# TSOC_GROVEY_I2CHUB_R1_0.net
KiCad netlist of a schematic drawn in EAGLE
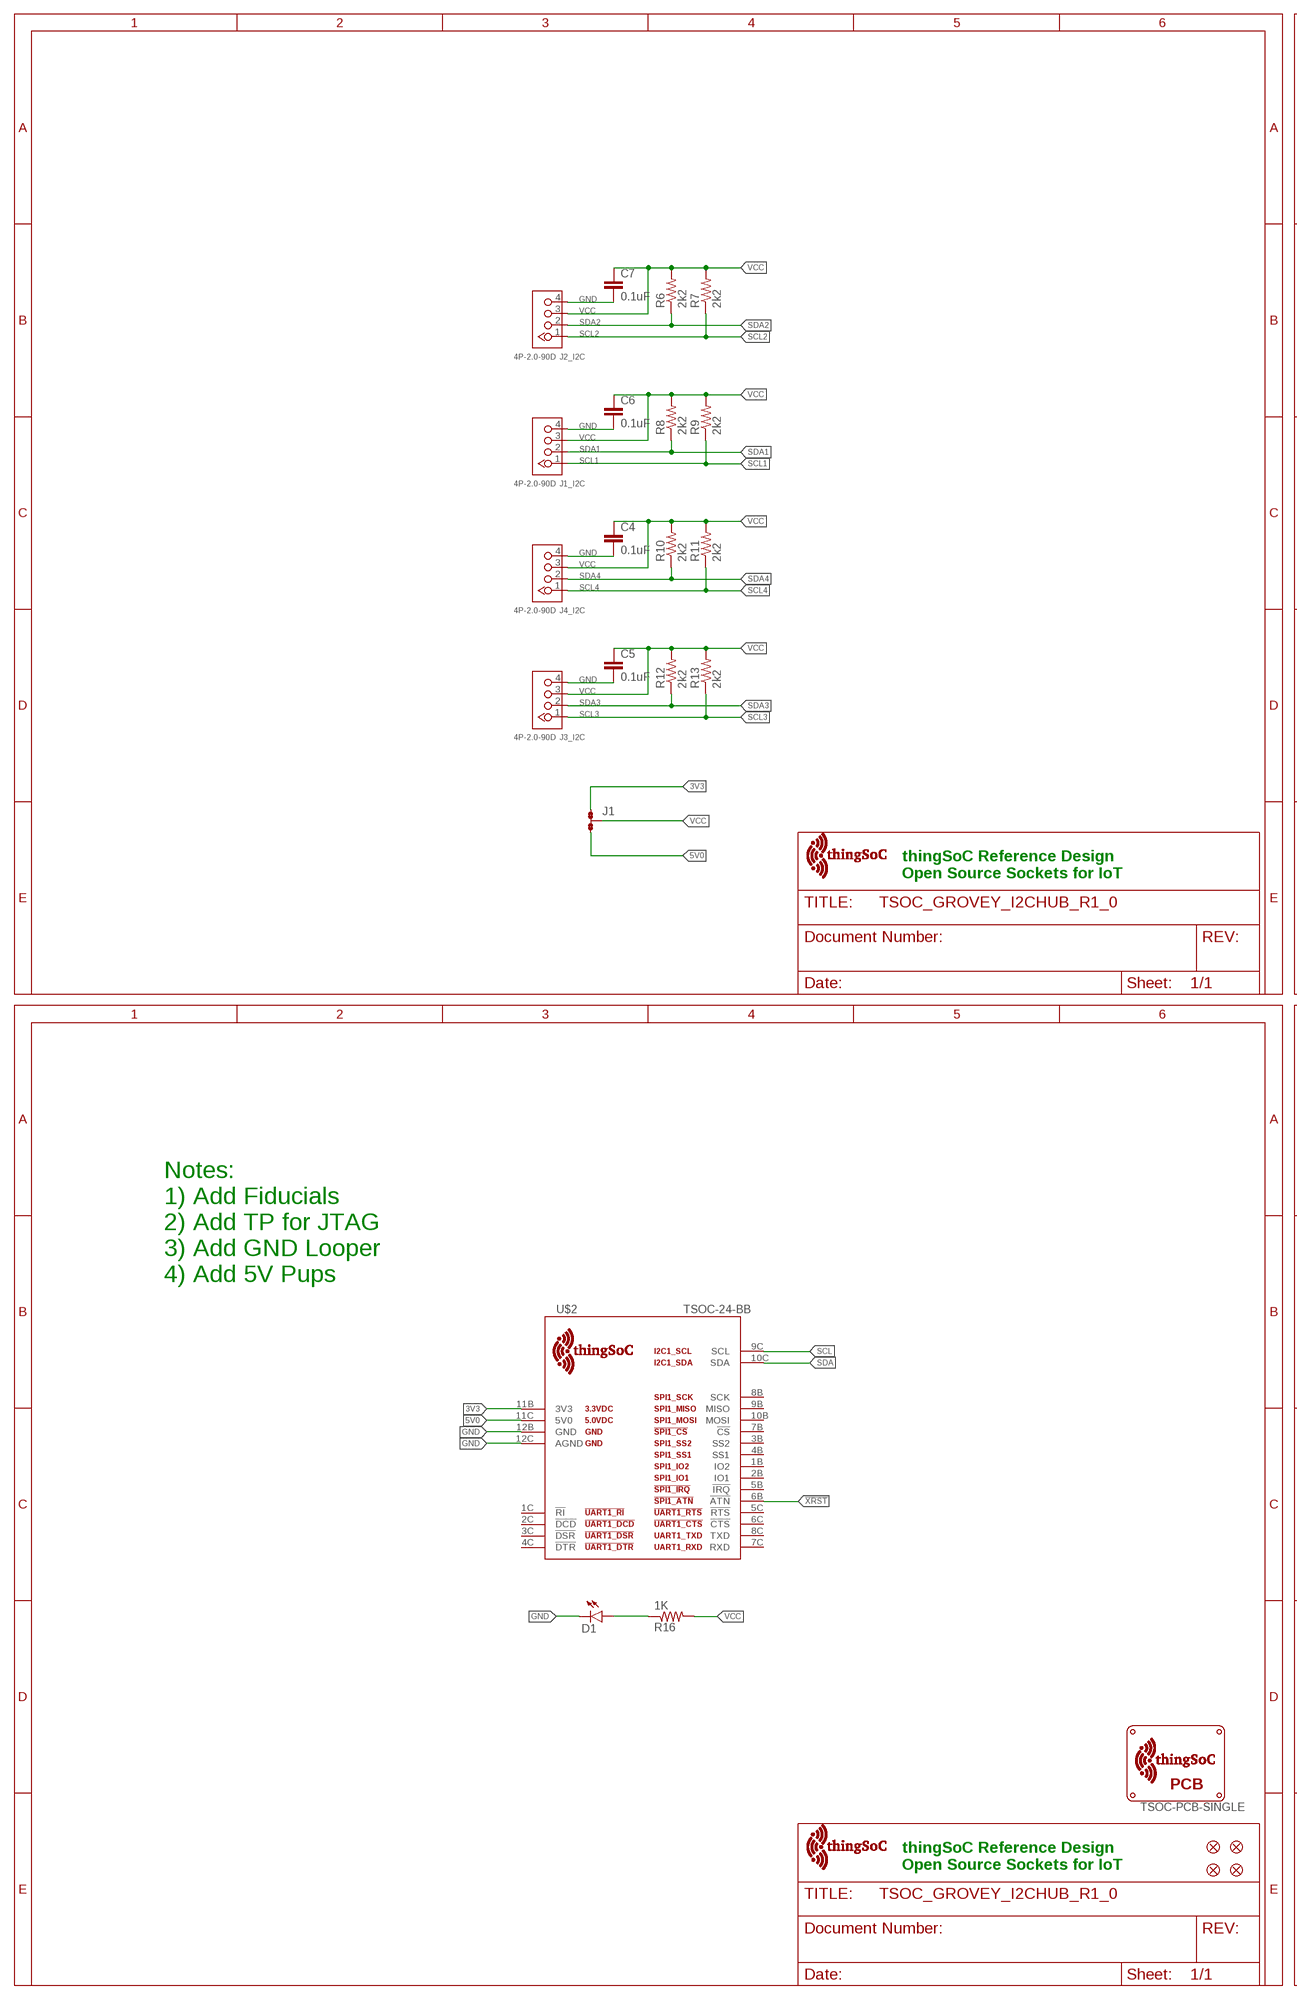
[diagram p0: schematic, sheet 1, part 1 of 2]
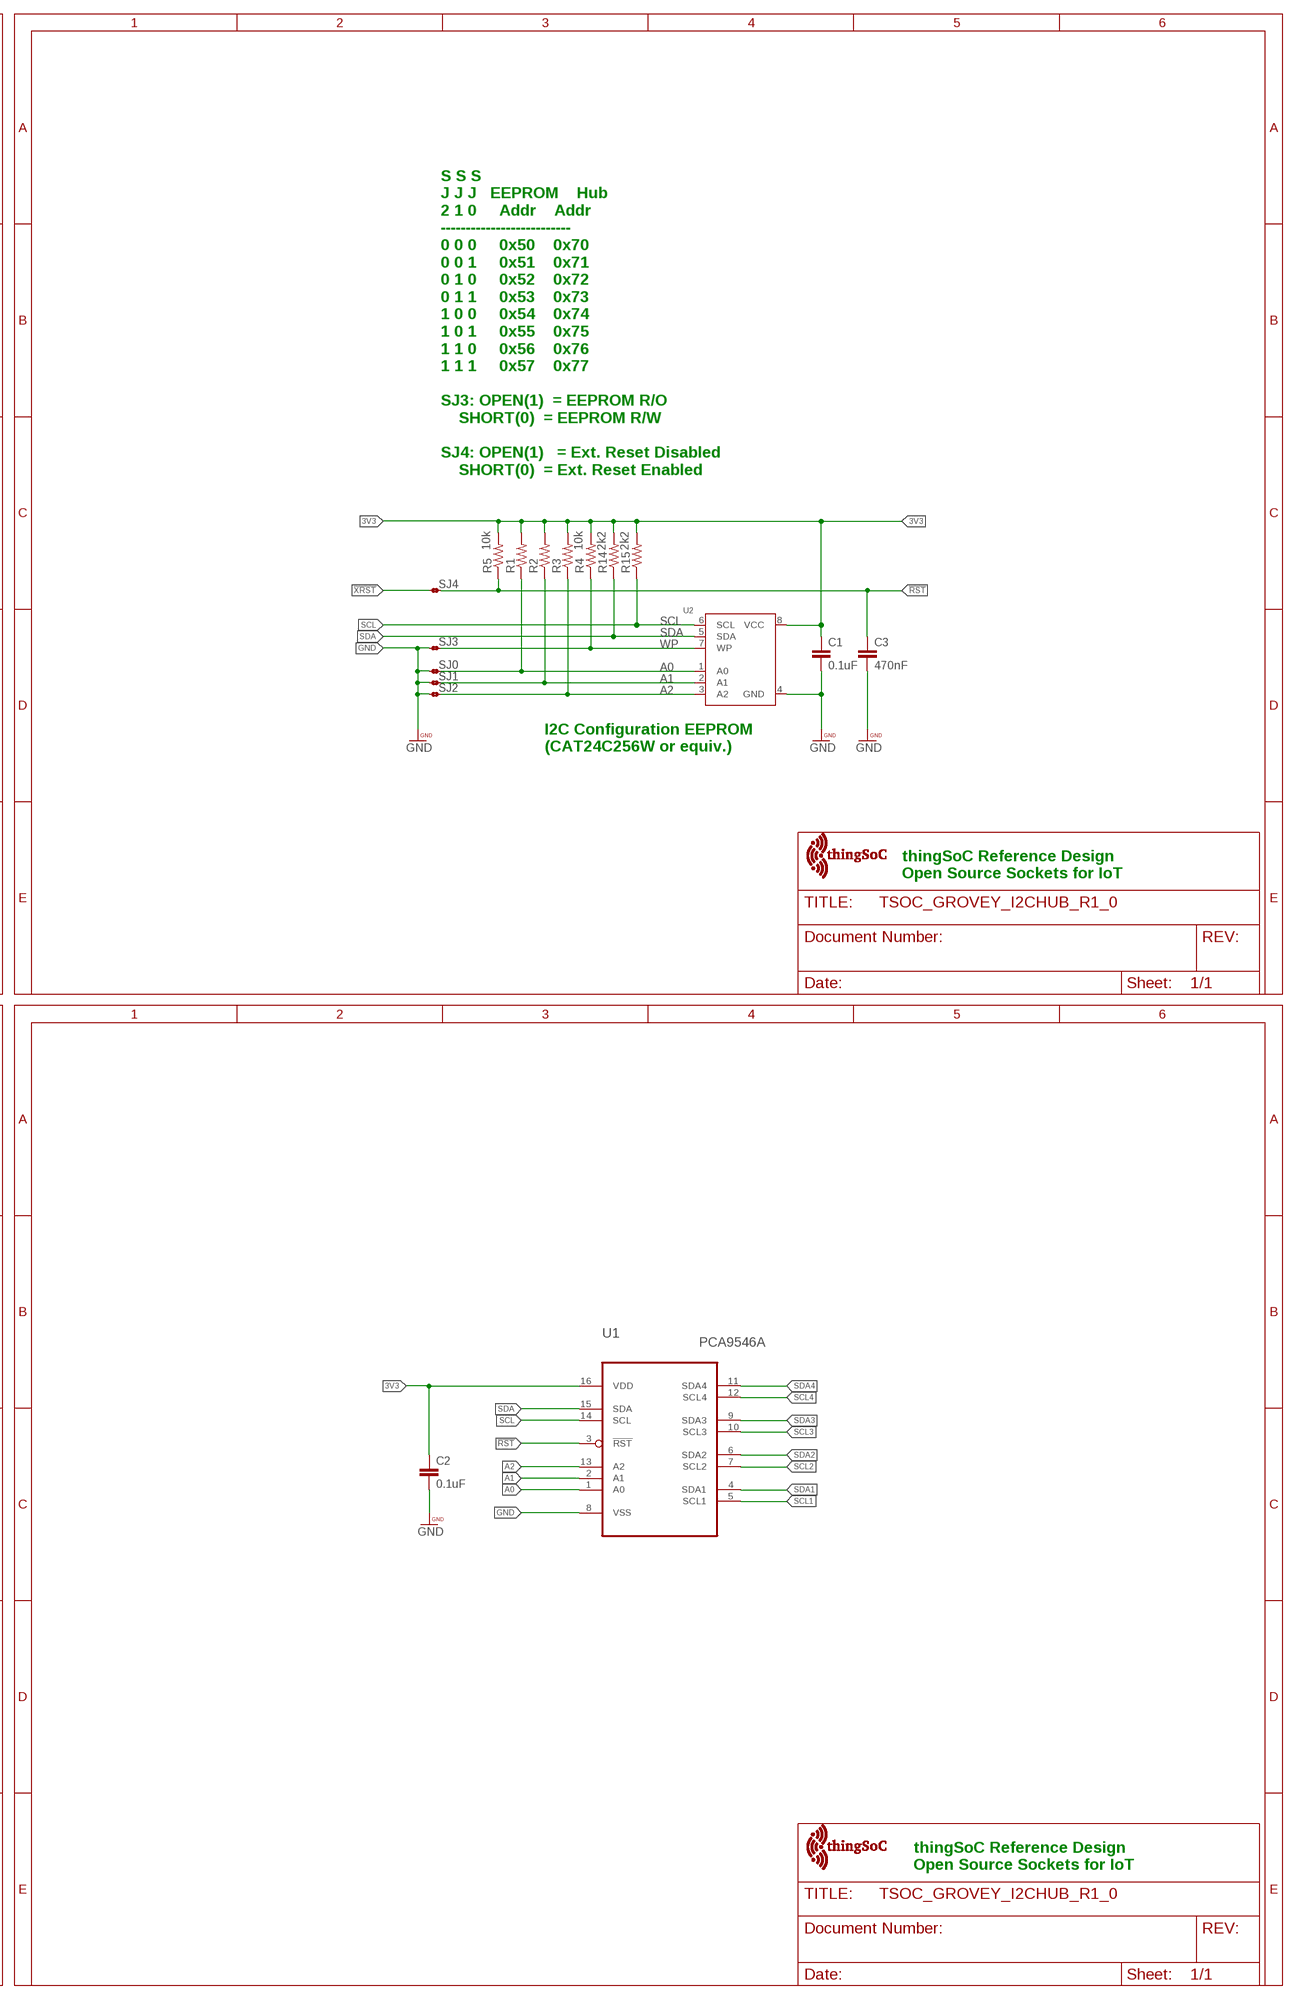
[diagram p1: schematic, sheet 1, part 2 of 2]

(export (version "E")
  (design (tool "Eeschema 10.0.6"))
  (components
    (comp (ref "C1")
      (value "0.1uF")
      (footprint "eagle-import:0603-CAP")
      (libsource (lib "eagle-import") (part "CAP0603-CAP"))
    )
    (comp (ref "C2")
      (value "0.1uF")
      (footprint "eagle-import:0603-CAP")
      (libsource (lib "eagle-import") (part "CAP0603-CAP"))
    )
    (comp (ref "C3")
      (value "470nF")
      (footprint "eagle-import:0603-CAP")
      (libsource (lib "eagle-import") (part "CAP0603-CAP"))
    )
    (comp (ref "C4")
      (value "0.1uF")
      (footprint "eagle-import:0603-CAP")
      (libsource (lib "eagle-import") (part "CAP0603-CAP"))
    )
    (comp (ref "C5")
      (value "0.1uF")
      (footprint "eagle-import:0603-CAP")
      (libsource (lib "eagle-import") (part "CAP0603-CAP"))
    )
    (comp (ref "C6")
      (value "0.1uF")
      (footprint "eagle-import:0603-CAP")
      (libsource (lib "eagle-import") (part "CAP0603-CAP"))
    )
    (comp (ref "C7")
      (value "0.1uF")
      (footprint "eagle-import:0603-CAP")
      (libsource (lib "eagle-import") (part "CAP0603-CAP"))
    )
    (comp (ref "D1")
      (value "LED0603")
      (footprint "eagle-import:LED-0603")
      (libsource (lib "eagle-import") (part "LED0603"))
    )
    (comp (ref "FID1")
      (value "FIDUCIALUFIDUCIAL")
      (footprint "eagle-import:MICRO-FIDUCIAL")
      (libsource (lib "eagle-import") (part "FIDUCIALUFIDUCIAL"))
    )
    (comp (ref "FID2")
      (value "FIDUCIALUFIDUCIAL")
      (footprint "eagle-import:MICRO-FIDUCIAL")
      (libsource (lib "eagle-import") (part "FIDUCIALUFIDUCIAL"))
    )
    (comp (ref "FID3")
      (value "FIDUCIALUFIDUCIAL")
      (footprint "eagle-import:MICRO-FIDUCIAL")
      (libsource (lib "eagle-import") (part "FIDUCIALUFIDUCIAL"))
    )
    (comp (ref "FID4")
      (value "FIDUCIALUFIDUCIAL")
      (footprint "eagle-import:MICRO-FIDUCIAL")
      (libsource (lib "eagle-import") (part "FIDUCIALUFIDUCIAL"))
    )
    (comp (ref "J1")
      (value "JMP-3-NO-PTH")
      (footprint "eagle-import:JMP-3-NO-PTH-2.54")
      (libsource (lib "eagle-import") (part "JMP-3-NO-PTH"))
    )
    (comp (ref "J1_I2C")
      (value "4P-2.0-90D")
      (footprint "eagle-import:HW4-2.0-90D")
      (libsource (lib "eagle-import") (part "GROVE-CONNECTOR-DIP-90D(4P-2.0)"))
    )
    (comp (ref "J2_I2C")
      (value "4P-2.0-90D")
      (footprint "eagle-import:HW4-2.0-90D")
      (libsource (lib "eagle-import") (part "GROVE-CONNECTOR-DIP-90D(4P-2.0)"))
    )
    (comp (ref "J3_I2C")
      (value "4P-2.0-90D")
      (footprint "eagle-import:HW4-2.0-90D")
      (libsource (lib "eagle-import") (part "GROVE-CONNECTOR-DIP-90D(4P-2.0)"))
    )
    (comp (ref "J4_I2C")
      (value "4P-2.0-90D")
      (footprint "eagle-import:HW4-2.0-90D")
      (libsource (lib "eagle-import") (part "GROVE-CONNECTOR-DIP-90D(4P-2.0)"))
    )
    (comp (ref "R1")
      (value "RESISTOR0603-RES")
      (footprint "eagle-import:0603-RES")
      (libsource (lib "eagle-import") (part "RESISTOR0603-RES"))
    )
    (comp (ref "R2")
      (value "RESISTOR0603-RES")
      (footprint "eagle-import:0603-RES")
      (libsource (lib "eagle-import") (part "RESISTOR0603-RES"))
    )
    (comp (ref "R3")
      (value "RESISTOR0603-RES")
      (footprint "eagle-import:0603-RES")
      (libsource (lib "eagle-import") (part "RESISTOR0603-RES"))
    )
    (comp (ref "R4")
      (value "10k")
      (footprint "eagle-import:0603-RES")
      (libsource (lib "eagle-import") (part "RESISTOR0603-RES"))
    )
    (comp (ref "R5")
      (value "10k")
      (footprint "eagle-import:0603-RES")
      (libsource (lib "eagle-import") (part "RESISTOR0603-RES"))
    )
    (comp (ref "R6")
      (value "2k2")
      (footprint "eagle-import:0603-RES")
      (libsource (lib "eagle-import") (part "RESISTOR0603-RES"))
    )
    (comp (ref "R7")
      (value "2k2")
      (footprint "eagle-import:0603-RES")
      (libsource (lib "eagle-import") (part "RESISTOR0603-RES"))
    )
    (comp (ref "R8")
      (value "2k2")
      (footprint "eagle-import:0603-RES")
      (libsource (lib "eagle-import") (part "RESISTOR0603-RES"))
    )
    (comp (ref "R9")
      (value "2k2")
      (footprint "eagle-import:0603-RES")
      (libsource (lib "eagle-import") (part "RESISTOR0603-RES"))
    )
    (comp (ref "R10")
      (value "2k2")
      (footprint "eagle-import:0603-RES")
      (libsource (lib "eagle-import") (part "RESISTOR0603-RES"))
    )
    (comp (ref "R11")
      (value "2k2")
      (footprint "eagle-import:0603-RES")
      (libsource (lib "eagle-import") (part "RESISTOR0603-RES"))
    )
    (comp (ref "R12")
      (value "2k2")
      (footprint "eagle-import:0603-RES")
      (libsource (lib "eagle-import") (part "RESISTOR0603-RES"))
    )
    (comp (ref "R13")
      (value "2k2")
      (footprint "eagle-import:0603-RES")
      (libsource (lib "eagle-import") (part "RESISTOR0603-RES"))
    )
    (comp (ref "R14")
      (value "2k2")
      (footprint "eagle-import:0603-RES")
      (libsource (lib "eagle-import") (part "RESISTOR0603-RES"))
    )
    (comp (ref "R15")
      (value "2k2")
      (footprint "eagle-import:0603-RES")
      (libsource (lib "eagle-import") (part "RESISTOR0603-RES"))
    )
    (comp (ref "R16")
      (value "1K")
      (footprint "eagle-import:0603-RES")
      (libsource (lib "eagle-import") (part "RESISTOR_SFE0603-RES"))
    )
    (comp (ref "SJ0")
      (value "JMP-2-NO")
      (footprint "eagle-import:JMP-2-NO")
      (libsource (lib "eagle-import") (part "JMP-2-NO"))
    )
    (comp (ref "SJ1")
      (value "JMP-2-NO")
      (footprint "eagle-import:JMP-2-NO")
      (libsource (lib "eagle-import") (part "JMP-2-NO"))
    )
    (comp (ref "SJ2")
      (value "JMP-2-NO")
      (footprint "eagle-import:JMP-2-NO")
      (libsource (lib "eagle-import") (part "JMP-2-NO"))
    )
    (comp (ref "SJ3")
      (value "JMP-2-NO")
      (footprint "eagle-import:JMP-2-NO")
      (libsource (lib "eagle-import") (part "JMP-2-NO"))
    )
    (comp (ref "SJ4")
      (value "JMP-2-NO")
      (footprint "eagle-import:JMP-2-NO")
      (libsource (lib "eagle-import") (part "JMP-2-NO"))
    )
    (comp (ref "U$1")
      (value "TSOC-PCB-SINGLE")
      (footprint "eagle-import:TSOC-BB-BRD-DIM")
      (libsource (lib "eagle-import") (part "TSOC-PCB-SINGLE"))
    )
    (comp (ref "U$2")
      (value "TSOC-24-BB")
      (footprint "eagle-import:TSOC-BB-S24")
      (libsource (lib "eagle-import") (part "TSOC-24-BB"))
    )
    (comp (ref "U$7")
      (value "TSOC-LOGO-SMALL")
      (footprint "eagle-import:TSOC-LOGO-SML")
      (libsource (lib "eagle-import") (part "TSOC-LOGO-SMALL"))
    )
    (comp (ref "U$9")
      (value "TSOC-LOGO-SMALL")
      (footprint "eagle-import:TSOC-LOGO-SML")
      (libsource (lib "eagle-import") (part "TSOC-LOGO-SMALL"))
    )
    (comp (ref "U$100")
      (value "TSOC-LOGO-SMALL")
      (footprint "eagle-import:TSOC-LOGO-SML")
      (libsource (lib "eagle-import") (part "TSOC-LOGO-SMALL"))
    )
    (comp (ref "U$101")
      (value "TSOC-LOGO-LRG")
      (footprint "eagle-import:TSOC-LOGO-LRG")
      (libsource (lib "eagle-import") (part "TSOC-LOGO-LRG"))
    )
    (comp (ref "U1")
      (value "PCA9546A")
      (footprint "eagle-import:SOP65P640X110-16N")
      (fields (field (name "MPN") "PCA9546APW,112"))
      (libsource (lib "eagle-import") (part "PCA9546A"))
    )
    (comp (ref "U2")
      (value "EEPROM_I2C_SOIC8_GENERIC")
      (footprint "eagle-import:SOIC8_150MIL")
      (libsource (lib "eagle-import") (part "EEPROM_I2C_SOIC8_GENERIC"))
    )
  )
  (nets
    (net (code "1") (name "/WP") (class "Default")
      (node (ref "R4") (pin "1") (pinfunction "1_1") (pintype "passive"))
      (node (ref "SJ3") (pin "2") (pinfunction "2_2") (pintype "passive"))
      (node (ref "U2") (pin "7") (pinfunction "WP_7") (pintype "input"))
    )
    (net (code "2") (name "/~{RST}") (class "Default")
      (node (ref "C3") (pin "1") (pinfunction "1_1") (pintype "passive"))
      (node (ref "R5") (pin "1") (pinfunction "1_1") (pintype "passive"))
      (node (ref "SJ4") (pin "1") (pinfunction "1_1") (pintype "passive"))
      (node (ref "U1") (pin "3") (pinfunction "~{RST}_3") (pintype "input"))
    )
    (net (code "3") (name "/~{XRST}") (class "Default")
      (node (ref "SJ4") (pin "2") (pinfunction "2_2") (pintype "passive"))
      (node (ref "U$2") (pin "6B") (pinfunction "~{ATN}_6B") (pintype "bidirectional"))
    )
    (net (code "4") (name "3V3") (class "Default")
      (node (ref "C1") (pin "1") (pinfunction "1_1") (pintype "passive"))
      (node (ref "C2") (pin "1") (pinfunction "1_1") (pintype "passive"))
      (node (ref "J1") (pin "1") (pinfunction "1_1") (pintype "passive"))
      (node (ref "R1") (pin "2") (pinfunction "2_2") (pintype "passive"))
      (node (ref "R14") (pin "2") (pinfunction "2_2") (pintype "passive"))
      (node (ref "R15") (pin "2") (pinfunction "2_2") (pintype "passive"))
      (node (ref "R2") (pin "2") (pinfunction "2_2") (pintype "passive"))
      (node (ref "R3") (pin "2") (pinfunction "2_2") (pintype "passive"))
      (node (ref "R4") (pin "2") (pinfunction "2_2") (pintype "passive"))
      (node (ref "R5") (pin "2") (pinfunction "2_2") (pintype "passive"))
      (node (ref "U$2") (pin "11B") (pinfunction "3V3_11B") (pintype "bidirectional"))
      (node (ref "U1") (pin "16") (pinfunction "VDD_16") (pintype "power_in"))
      (node (ref "U2") (pin "8") (pinfunction "VCC_8") (pintype "power_in"))
    )
    (net (code "5") (name "5V0") (class "Default")
      (node (ref "J1") (pin "3") (pinfunction "3_3") (pintype "passive"))
      (node (ref "U$2") (pin "11C") (pinfunction "5V0_11C") (pintype "bidirectional"))
    )
    (net (code "6") (name "A0") (class "Default")
      (node (ref "R1") (pin "1") (pinfunction "1_1") (pintype "passive"))
      (node (ref "SJ0") (pin "2") (pinfunction "2_2") (pintype "passive"))
      (node (ref "U1") (pin "1") (pinfunction "A0_1") (pintype "input"))
      (node (ref "U2") (pin "1") (pinfunction "A0_1") (pintype "input"))
    )
    (net (code "7") (name "A1") (class "Default")
      (node (ref "R2") (pin "1") (pinfunction "1_1") (pintype "passive"))
      (node (ref "SJ1") (pin "2") (pinfunction "2_2") (pintype "passive"))
      (node (ref "U1") (pin "2") (pinfunction "A1_2") (pintype "input"))
      (node (ref "U2") (pin "2") (pinfunction "A1_2") (pintype "input"))
    )
    (net (code "8") (name "A2") (class "Default")
      (node (ref "R3") (pin "1") (pinfunction "1_1") (pintype "passive"))
      (node (ref "SJ2") (pin "2") (pinfunction "2_2") (pintype "passive"))
      (node (ref "U1") (pin "13") (pinfunction "A2_13") (pintype "input"))
      (node (ref "U2") (pin "3") (pinfunction "A2_3") (pintype "input"))
    )
    (net (code "9") (name "GND") (class "Default")
      (node (ref "C1") (pin "2") (pinfunction "2_2") (pintype "passive"))
      (node (ref "C2") (pin "2") (pinfunction "2_2") (pintype "passive"))
      (node (ref "C3") (pin "2") (pinfunction "2_2") (pintype "passive"))
      (node (ref "C4") (pin "2") (pinfunction "2_2") (pintype "passive"))
      (node (ref "C5") (pin "2") (pinfunction "2_2") (pintype "passive"))
      (node (ref "C6") (pin "2") (pinfunction "2_2") (pintype "passive"))
      (node (ref "C7") (pin "2") (pinfunction "2_2") (pintype "passive"))
      (node (ref "D1") (pin "C") (pinfunction "C_C") (pintype "passive"))
      (node (ref "J1_I2C") (pin "4") (pinfunction "4_4") (pintype "bidirectional"))
      (node (ref "J2_I2C") (pin "4") (pinfunction "4_4") (pintype "bidirectional"))
      (node (ref "J3_I2C") (pin "4") (pinfunction "4_4") (pintype "bidirectional"))
      (node (ref "J4_I2C") (pin "4") (pinfunction "4_4") (pintype "bidirectional"))
      (node (ref "SJ0") (pin "1") (pinfunction "1_1") (pintype "passive"))
      (node (ref "SJ1") (pin "1") (pinfunction "1_1") (pintype "passive"))
      (node (ref "SJ2") (pin "1") (pinfunction "1_1") (pintype "passive"))
      (node (ref "SJ3") (pin "1") (pinfunction "1_1") (pintype "passive"))
      (node (ref "U$2") (pin "12B") (pinfunction "GND_12B") (pintype "bidirectional"))
      (node (ref "U$2") (pin "12C") (pinfunction "AGND_12C") (pintype "bidirectional"))
      (node (ref "U1") (pin "8") (pinfunction "VSS_8") (pintype "passive"))
      (node (ref "U2") (pin "4") (pinfunction "GND_4") (pintype "power_in"))
    )
    (net (code "10") (name "Net-(D1-PadA)") (class "Default")
      (node (ref "D1") (pin "A") (pinfunction "A_A") (pintype "passive"))
      (node (ref "R16") (pin "1") (pinfunction "1_1") (pintype "passive"))
    )
    (net (code "11") (name "SCL") (class "Default")
      (node (ref "R15") (pin "1") (pinfunction "1_1") (pintype "passive"))
      (node (ref "U$2") (pin "9C") (pinfunction "SCL_9C") (pintype "bidirectional"))
      (node (ref "U1") (pin "14") (pinfunction "SCL_14") (pintype "bidirectional"))
      (node (ref "U2") (pin "6") (pinfunction "SCL_6") (pintype "input"))
    )
    (net (code "12") (name "SCL1") (class "Default")
      (node (ref "J1_I2C") (pin "1") (pinfunction "1_1") (pintype "bidirectional"))
      (node (ref "R9") (pin "1") (pinfunction "1_1") (pintype "passive"))
      (node (ref "U1") (pin "5") (pinfunction "SCL1_5") (pintype "input"))
    )
    (net (code "13") (name "SCL2") (class "Default")
      (node (ref "J2_I2C") (pin "1") (pinfunction "1_1") (pintype "bidirectional"))
      (node (ref "R7") (pin "1") (pinfunction "1_1") (pintype "passive"))
      (node (ref "U1") (pin "7") (pinfunction "SCL2_7") (pintype "input"))
    )
    (net (code "14") (name "SCL3") (class "Default")
      (node (ref "J3_I2C") (pin "1") (pinfunction "1_1") (pintype "bidirectional"))
      (node (ref "R13") (pin "1") (pinfunction "1_1") (pintype "passive"))
      (node (ref "U1") (pin "10") (pinfunction "SCL3_10") (pintype "input"))
    )
    (net (code "15") (name "SCL4") (class "Default")
      (node (ref "J4_I2C") (pin "1") (pinfunction "1_1") (pintype "bidirectional"))
      (node (ref "R11") (pin "1") (pinfunction "1_1") (pintype "passive"))
      (node (ref "U1") (pin "12") (pinfunction "SCL4_12") (pintype "input"))
    )
    (net (code "16") (name "SDA") (class "Default")
      (node (ref "R14") (pin "1") (pinfunction "1_1") (pintype "passive"))
      (node (ref "U$2") (pin "10C") (pinfunction "SDA_10C") (pintype "bidirectional"))
      (node (ref "U1") (pin "15") (pinfunction "SDA_15") (pintype "bidirectional"))
      (node (ref "U2") (pin "5") (pinfunction "SDA_5") (pintype "bidirectional"))
    )
    (net (code "17") (name "SDA1") (class "Default")
      (node (ref "J1_I2C") (pin "2") (pinfunction "2_2") (pintype "bidirectional"))
      (node (ref "R8") (pin "1") (pinfunction "1_1") (pintype "passive"))
      (node (ref "U1") (pin "4") (pinfunction "SDA1_4") (pintype "input"))
    )
    (net (code "18") (name "SDA2") (class "Default")
      (node (ref "J2_I2C") (pin "2") (pinfunction "2_2") (pintype "bidirectional"))
      (node (ref "R6") (pin "1") (pinfunction "1_1") (pintype "passive"))
      (node (ref "U1") (pin "6") (pinfunction "SDA2_6") (pintype "input"))
    )
    (net (code "19") (name "SDA3") (class "Default")
      (node (ref "J3_I2C") (pin "2") (pinfunction "2_2") (pintype "bidirectional"))
      (node (ref "R12") (pin "1") (pinfunction "1_1") (pintype "passive"))
      (node (ref "U1") (pin "9") (pinfunction "SDA3_9") (pintype "input"))
    )
    (net (code "20") (name "SDA4") (class "Default")
      (node (ref "J4_I2C") (pin "2") (pinfunction "2_2") (pintype "bidirectional"))
      (node (ref "R10") (pin "1") (pinfunction "1_1") (pintype "passive"))
      (node (ref "U1") (pin "11") (pinfunction "SDA4_11") (pintype "input"))
    )
    (net (code "21") (name "VCC") (class "Default")
      (node (ref "C4") (pin "1") (pinfunction "1_1") (pintype "passive"))
      (node (ref "C5") (pin "1") (pinfunction "1_1") (pintype "passive"))
      (node (ref "C6") (pin "1") (pinfunction "1_1") (pintype "passive"))
      (node (ref "C7") (pin "1") (pinfunction "1_1") (pintype "passive"))
      (node (ref "J1") (pin "2") (pinfunction "2_2") (pintype "passive"))
      (node (ref "J1_I2C") (pin "3") (pinfunction "3_3") (pintype "bidirectional"))
      (node (ref "J2_I2C") (pin "3") (pinfunction "3_3") (pintype "bidirectional"))
      (node (ref "J3_I2C") (pin "3") (pinfunction "3_3") (pintype "bidirectional"))
      (node (ref "J4_I2C") (pin "3") (pinfunction "3_3") (pintype "bidirectional"))
      (node (ref "R10") (pin "2") (pinfunction "2_2") (pintype "passive"))
      (node (ref "R11") (pin "2") (pinfunction "2_2") (pintype "passive"))
      (node (ref "R12") (pin "2") (pinfunction "2_2") (pintype "passive"))
      (node (ref "R13") (pin "2") (pinfunction "2_2") (pintype "passive"))
      (node (ref "R16") (pin "2") (pinfunction "2_2") (pintype "passive"))
      (node (ref "R6") (pin "2") (pinfunction "2_2") (pintype "passive"))
      (node (ref "R7") (pin "2") (pinfunction "2_2") (pintype "passive"))
      (node (ref "R8") (pin "2") (pinfunction "2_2") (pintype "passive"))
      (node (ref "R9") (pin "2") (pinfunction "2_2") (pintype "passive"))
    )
    (net (code "22") (name "unconnected-(U$2-IO1-Pad2B)") (class "Default")
      (node (ref "U$2") (pin "2B") (pinfunction "IO1_2B") (pintype "bidirectional"))
    )
    (net (code "23") (name "unconnected-(U$2-IO2-Pad1B)") (class "Default")
      (node (ref "U$2") (pin "1B") (pinfunction "IO2_1B") (pintype "bidirectional"))
    )
    (net (code "24") (name "unconnected-(U$2-MISO-Pad9B)") (class "Default")
      (node (ref "U$2") (pin "9B") (pinfunction "MISO_9B") (pintype "bidirectional"))
    )
    (net (code "25") (name "unconnected-(U$2-MOSI-Pad10B)") (class "Default")
      (node (ref "U$2") (pin "10B") (pinfunction "MOSI_10B") (pintype "bidirectional"))
    )
    (net (code "26") (name "unconnected-(U$2-RXD-Pad7C)") (class "Default")
      (node (ref "U$2") (pin "7C") (pinfunction "RXD_7C") (pintype "bidirectional"))
    )
    (net (code "27") (name "unconnected-(U$2-SCK-Pad8B)") (class "Default")
      (node (ref "U$2") (pin "8B") (pinfunction "SCK_8B") (pintype "bidirectional"))
    )
    (net (code "28") (name "unconnected-(U$2-SS1-Pad4B)") (class "Default")
      (node (ref "U$2") (pin "4B") (pinfunction "SS1_4B") (pintype "bidirectional"))
    )
    (net (code "29") (name "unconnected-(U$2-SS2-Pad3B)") (class "Default")
      (node (ref "U$2") (pin "3B") (pinfunction "SS2_3B") (pintype "bidirectional"))
    )
    (net (code "30") (name "unconnected-(U$2-TXD-Pad8C)") (class "Default")
      (node (ref "U$2") (pin "8C") (pinfunction "TXD_8C") (pintype "bidirectional"))
    )
    (net (code "31") (name "unconnected-(U$2-~{CS}-Pad7B)") (class "Default")
      (node (ref "U$2") (pin "7B") (pinfunction "~{CS}_7B") (pintype "bidirectional"))
    )
    (net (code "32") (name "unconnected-(U$2-~{CTS}-Pad6C)") (class "Default")
      (node (ref "U$2") (pin "6C") (pinfunction "~{CTS}_6C") (pintype "bidirectional"))
    )
    (net (code "33") (name "unconnected-(U$2-~{DCD}-Pad2C)") (class "Default")
      (node (ref "U$2") (pin "2C") (pinfunction "~{DCD}_2C") (pintype "bidirectional"))
    )
    (net (code "34") (name "unconnected-(U$2-~{DSR}-Pad3C)") (class "Default")
      (node (ref "U$2") (pin "3C") (pinfunction "~{DSR}_3C") (pintype "bidirectional"))
    )
    (net (code "35") (name "unconnected-(U$2-~{DTR}-Pad4C)") (class "Default")
      (node (ref "U$2") (pin "4C") (pinfunction "~{DTR}_4C") (pintype "bidirectional"))
    )
    (net (code "36") (name "unconnected-(U$2-~{IRQ}-Pad5B)") (class "Default")
      (node (ref "U$2") (pin "5B") (pinfunction "~{IRQ}_5B") (pintype "bidirectional"))
    )
    (net (code "37") (name "unconnected-(U$2-~{RI}-Pad1C)") (class "Default")
      (node (ref "U$2") (pin "1C") (pinfunction "~{RI}_1C") (pintype "bidirectional"))
    )
    (net (code "38") (name "unconnected-(U$2-~{RTS}-Pad5C)") (class "Default")
      (node (ref "U$2") (pin "5C") (pinfunction "~{RTS}_5C") (pintype "bidirectional"))
    )
  )
)
